# MF_badge_2021_rev_B.net
KiCad netlist of a schematic drawn in EAGLE
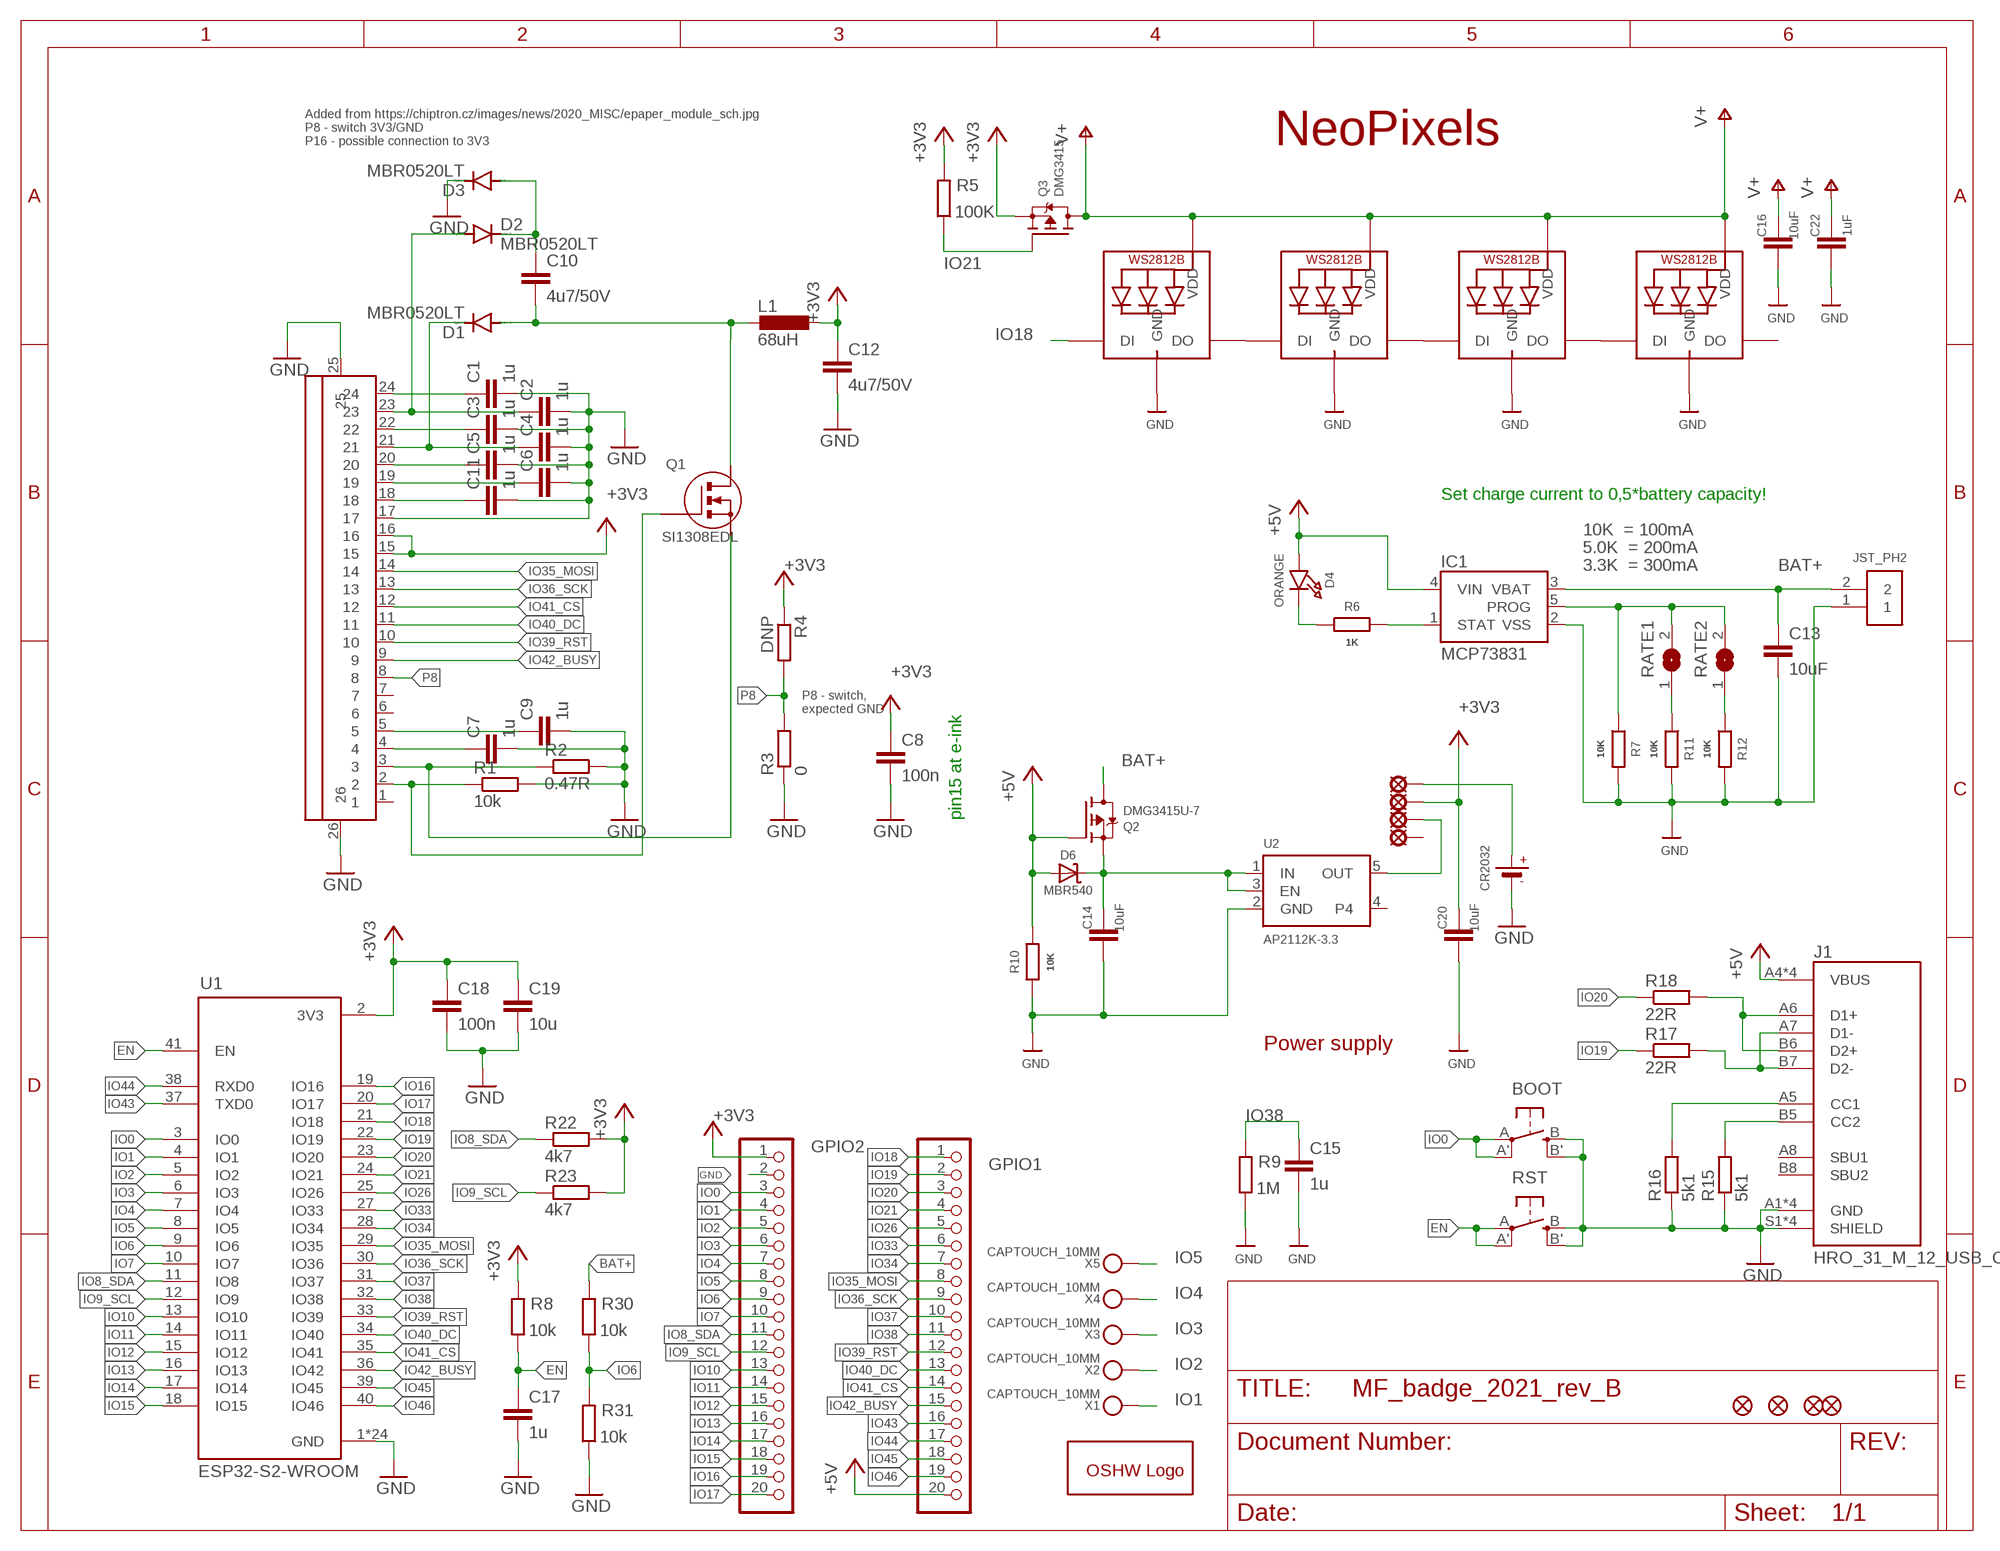
[diagram p0: schematic, sheet 1]

(export (version "E")
  (design (tool "Eeschema 10.0.6"))
  (components
    (comp (ref "BOOT")
      (value "BUTTON_KMR2_4.6X2.8")
      (footprint "eagle-import:BUTTON_KMR2_4.6X2.8")
      (libsource (lib "eagle-import") (part "BUTTON_KMR2_4.6X2.8"))
    )
    (comp (ref "C1")
      (value "1u")
      (footprint "eagle-import:C0805")
      (libsource (lib "eagle-import") (part "C-EUC0805"))
    )
    (comp (ref "C2")
      (value "1u")
      (footprint "eagle-import:C0805")
      (libsource (lib "eagle-import") (part "C-EUC0805"))
    )
    (comp (ref "C3")
      (value "1u")
      (footprint "eagle-import:C0805")
      (libsource (lib "eagle-import") (part "C-EUC0805"))
    )
    (comp (ref "C4")
      (value "1u")
      (footprint "eagle-import:C0805")
      (libsource (lib "eagle-import") (part "C-EUC0805"))
    )
    (comp (ref "C5")
      (value "1u")
      (footprint "eagle-import:C0805")
      (libsource (lib "eagle-import") (part "C-EUC0805"))
    )
    (comp (ref "C6")
      (value "1u")
      (footprint "eagle-import:C0805")
      (libsource (lib "eagle-import") (part "C-EUC0805"))
    )
    (comp (ref "C7")
      (value "1u")
      (footprint "eagle-import:C0805")
      (libsource (lib "eagle-import") (part "C-EUC0805"))
    )
    (comp (ref "C8")
      (value "100n")
      (footprint "eagle-import:C0805")
      (libsource (lib "eagle-import") (part "C-EUC0805"))
    )
    (comp (ref "C9")
      (value "1u")
      (footprint "eagle-import:C0805")
      (libsource (lib "eagle-import") (part "C-EUC0805"))
    )
    (comp (ref "C10")
      (value "4u7/50V")
      (footprint "eagle-import:C0805")
      (libsource (lib "eagle-import") (part "C-EUC0805"))
    )
    (comp (ref "C11")
      (value "1u")
      (footprint "eagle-import:C0805")
      (libsource (lib "eagle-import") (part "C-EUC0805"))
    )
    (comp (ref "C12")
      (value "4u7/50V")
      (footprint "eagle-import:C0805")
      (libsource (lib "eagle-import") (part "C-EUC0805"))
    )
    (comp (ref "C13")
      (value "10uF")
      (footprint "eagle-import:C0805")
      (libsource (lib "eagle-import") (part "C-EUC0805"))
    )
    (comp (ref "C14")
      (value "10uF")
      (footprint "eagle-import:C0805")
      (libsource (lib "eagle-import") (part "C-EUC0805"))
    )
    (comp (ref "C15")
      (value "1u")
      (footprint "eagle-import:C0805")
      (libsource (lib "eagle-import") (part "C-EUC0805"))
    )
    (comp (ref "C16")
      (value "10uF")
      (footprint "eagle-import:C0805")
      (libsource (lib "eagle-import") (part "C-EUC0805"))
    )
    (comp (ref "C17")
      (value "1u")
      (footprint "eagle-import:C0805")
      (libsource (lib "eagle-import") (part "C-EUC0805"))
    )
    (comp (ref "C18")
      (value "100n")
      (footprint "eagle-import:C0805")
      (libsource (lib "eagle-import") (part "C-EUC0805"))
    )
    (comp (ref "C19")
      (value "10u")
      (footprint "eagle-import:C1206")
      (libsource (lib "eagle-import") (part "C-EUC1206"))
    )
    (comp (ref "C20")
      (value "10uF")
      (footprint "eagle-import:C0805")
      (libsource (lib "eagle-import") (part "C-EUC0805"))
    )
    (comp (ref "C22")
      (value "1uF")
      (footprint "eagle-import:C0805")
      (libsource (lib "eagle-import") (part "C-EUC0805"))
    )
    (comp (ref "CR2032")
      (value "BATTERYCR2032_BAT-HLD-001")
      (footprint "eagle-import:CR2032_SMT_BAT-HLD-001")
      (libsource (lib "eagle-import") (part "BATTERYCR2032_BAT-HLD-001"))
    )
    (comp (ref "D1")
      (value "MBR0520LT")
      (footprint "eagle-import:SOD123")
      (libsource (lib "eagle-import") (part "MBR0520LT"))
    )
    (comp (ref "D2")
      (value "MBR0520LT")
      (footprint "eagle-import:SOD123")
      (libsource (lib "eagle-import") (part "MBR0520LT"))
    )
    (comp (ref "D3")
      (value "MBR0520LT")
      (footprint "eagle-import:SOD123")
      (libsource (lib "eagle-import") (part "MBR0520LT"))
    )
    (comp (ref "D4")
      (value "ORANGE")
      (footprint "eagle-import:CHIPLED_0805_NOOUTLINE")
      (libsource (lib "eagle-import") (part "LED0805_NOOUTLINE"))
    )
    (comp (ref "D6")
      (value "MBR540")
      (footprint "eagle-import:SOD-123")
      (libsource (lib "eagle-import") (part "DIODE-SCHOTTKYSOD-123"))
    )
    (comp (ref "FID1")
      (value "FIDUCIAL_1MM")
      (footprint "eagle-import:FIDUCIAL_1MM")
      (libsource (lib "eagle-import") (part "FIDUCIAL_1MM"))
    )
    (comp (ref "FID2")
      (value "FIDUCIAL_1MM")
      (footprint "eagle-import:FIDUCIAL_1MM")
      (libsource (lib "eagle-import") (part "FIDUCIAL_1MM"))
    )
    (comp (ref "FID3")
      (value "FIDUCIAL_1MM")
      (footprint "eagle-import:FIDUCIAL_1MM")
      (libsource (lib "eagle-import") (part "FIDUCIAL_1MM"))
    )
    (comp (ref "FID4")
      (value "FIDUCIAL_1MM")
      (footprint "eagle-import:FIDUCIAL_1MM")
      (libsource (lib "eagle-import") (part "FIDUCIAL_1MM"))
    )
    (comp (ref "GOLD_ORB_SM1")
      (value "OSHWLOGO_")
      (footprint "eagle-import:OSHW_5MM_LOGO")
      (libsource (lib "eagle-import") (part "OSHWLOGO_"))
    )
    (comp (ref "GPIO1")
      (value "PINHD-1X20")
      (footprint "eagle-import:1X20")
      (libsource (lib "eagle-import") (part "PINHD-1X20"))
    )
    (comp (ref "GPIO2")
      (value "PINHD-1X20")
      (footprint "eagle-import:1X20")
      (libsource (lib "eagle-import") (part "PINHD-1X20"))
    )
    (comp (ref "IC1")
      (value "MCP73831")
      (footprint "eagle-import:SOT95P290X120-5")
      (libsource (lib "eagle-import") (part "MCP73831"))
    )
    (comp (ref "J1")
      (value "HRO_31_M_12_USB_C")
      (footprint "eagle-import:HRO_31_M_12_USB_C")
      (libsource (lib "eagle-import") (part "HRO_31_M_12_USB_C"))
    )
    (comp (ref "L1")
      (value "68uH")
      (footprint "eagle-import:L4532P")
      (libsource (lib "eagle-import") (part "L-EUL4532P"))
    )
    (comp (ref "LED2")
      (value "WS2812B5050")
      (footprint "eagle-import:WS2812B")
      (libsource (lib "eagle-import") (part "WS2812B5050"))
    )
    (comp (ref "LED3")
      (value "WS2812B5050")
      (footprint "eagle-import:WS2812B")
      (libsource (lib "eagle-import") (part "WS2812B5050"))
    )
    (comp (ref "LED4")
      (value "WS2812B5050")
      (footprint "eagle-import:WS2812B")
      (libsource (lib "eagle-import") (part "WS2812B5050"))
    )
    (comp (ref "LED5")
      (value "WS2812B5050")
      (footprint "eagle-import:WS2812B")
      (libsource (lib "eagle-import") (part "WS2812B5050"))
    )
    (comp (ref "LSP1")
      (value "MCS10B")
      (footprint "eagle-import:MCS10B")
      (libsource (lib "eagle-import") (part "MCS10B"))
    )
    (comp (ref "LSP2")
      (value "MCS10B")
      (footprint "eagle-import:MCS10B")
      (libsource (lib "eagle-import") (part "MCS10B"))
    )
    (comp (ref "LSP3")
      (value "MCS10B")
      (footprint "eagle-import:MCS10B")
      (libsource (lib "eagle-import") (part "MCS10B"))
    )
    (comp (ref "LSP4")
      (value "MCS10B")
      (footprint "eagle-import:MCS10B")
      (libsource (lib "eagle-import") (part "MCS10B"))
    )
    (comp (ref "Q1")
      (value "SI1308EDL")
      (footprint "eagle-import:SC-70")
      (libsource (lib "eagle-import") (part "SI1308EDL"))
    )
    (comp (ref "Q2")
      (value "DMG3415U-7")
      (footprint "eagle-import:SOT23-R")
      (libsource (lib "eagle-import") (part "MOSFET-P"))
    )
    (comp (ref "Q3")
      (value "DMG3415")
      (footprint "eagle-import:SOT23-R")
      (libsource (lib "eagle-import") (part "MOSFET-P"))
    )
    (comp (ref "R1")
      (value "10k")
      (footprint "eagle-import:R0805")
      (libsource (lib "eagle-import") (part "R-EU_R0805"))
    )
    (comp (ref "R2")
      (value "0.47R")
      (footprint "eagle-import:R0805")
      (libsource (lib "eagle-import") (part "R-EU_R0805"))
    )
    (comp (ref "R3")
      (value "0")
      (footprint "eagle-import:R0805")
      (libsource (lib "eagle-import") (part "R-EU_R0805"))
    )
    (comp (ref "R4")
      (value "DNP")
      (footprint "eagle-import:R0805")
      (libsource (lib "eagle-import") (part "R-EU_R0805"))
    )
    (comp (ref "R5")
      (value "100K")
      (footprint "eagle-import:R0805")
      (libsource (lib "eagle-import") (part "R-EU_R0805"))
    )
    (comp (ref "R6")
      (value "1K")
      (footprint "eagle-import:R0805")
      (libsource (lib "eagle-import") (part "R-EU_R0805"))
    )
    (comp (ref "R7")
      (value "10K")
      (footprint "eagle-import:R0805")
      (libsource (lib "eagle-import") (part "R-EU_R0805"))
    )
    (comp (ref "R8")
      (value "10k")
      (footprint "eagle-import:R0805")
      (libsource (lib "eagle-import") (part "R-EU_R0805"))
    )
    (comp (ref "R9")
      (value "1M")
      (footprint "eagle-import:R0805")
      (libsource (lib "eagle-import") (part "R-EU_R0805"))
    )
    (comp (ref "R10")
      (value "10K")
      (footprint "eagle-import:R0805")
      (libsource (lib "eagle-import") (part "R-EU_R0805"))
    )
    (comp (ref "R11")
      (value "10K")
      (footprint "eagle-import:R0805")
      (libsource (lib "eagle-import") (part "R-EU_R0805"))
    )
    (comp (ref "R12")
      (value "10K")
      (footprint "eagle-import:R0805")
      (libsource (lib "eagle-import") (part "R-EU_R0805"))
    )
    (comp (ref "R15")
      (value "5k1")
      (footprint "eagle-import:R0805")
      (libsource (lib "eagle-import") (part "R-EU_R0805"))
    )
    (comp (ref "R16")
      (value "5k1")
      (footprint "eagle-import:R0805")
      (libsource (lib "eagle-import") (part "R-EU_R0805"))
    )
    (comp (ref "R17")
      (value "22R")
      (footprint "eagle-import:R0805")
      (libsource (lib "eagle-import") (part "R-EU_R0805"))
    )
    (comp (ref "R18")
      (value "22R")
      (footprint "eagle-import:R0805")
      (libsource (lib "eagle-import") (part "R-EU_R0805"))
    )
    (comp (ref "R22")
      (value "4k7")
      (footprint "eagle-import:R0805")
      (libsource (lib "eagle-import") (part "R-EU_R0805"))
    )
    (comp (ref "R23")
      (value "4k7")
      (footprint "eagle-import:R0805")
      (libsource (lib "eagle-import") (part "R-EU_R0805"))
    )
    (comp (ref "R30")
      (value "10k")
      (footprint "eagle-import:R0805")
      (libsource (lib "eagle-import") (part "R-EU_R0805"))
    )
    (comp (ref "R31")
      (value "10k")
      (footprint "eagle-import:R0805")
      (libsource (lib "eagle-import") (part "R-EU_R0805"))
    )
    (comp (ref "RATE1")
      (value "SOLDERJUMPER")
      (footprint "eagle-import:SOLDERJUMPER_ARROW_NOPASTE")
      (libsource (lib "eagle-import") (part "SOLDERJUMPER"))
    )
    (comp (ref "RATE2")
      (value "SOLDERJUMPER")
      (footprint "eagle-import:SOLDERJUMPER_ARROW_NOPASTE")
      (libsource (lib "eagle-import") (part "SOLDERJUMPER"))
    )
    (comp (ref "RST")
      (value "BUTTON_KMR2_4.6X2.8")
      (footprint "eagle-import:BUTTON_KMR2_4.6X2.8")
      (libsource (lib "eagle-import") (part "BUTTON_KMR2_4.6X2.8"))
    )
    (comp (ref "U$1")
      (value "2.13_EINK")
      (footprint "eagle-import:2.13_EINK")
      (libsource (lib "eagle-import") (part "2.13_EINK"))
    )
    (comp (ref "U$8")
      (value "JST_PH2")
      (footprint "eagle-import:JSTPH2")
      (libsource (lib "eagle-import") (part "JST_PH2"))
    )
    (comp (ref "U1")
      (value "ESP32-S2-WROOM")
      (footprint "eagle-import:XCVR_ESP32-S2-WROOM")
      (fields (field (name "MF") "Espressif Systems"))
      (libsource (lib "eagle-import") (part "ESP32-S2-WROOM"))
    )
    (comp (ref "U2")
      (value "AP2112K-3.3")
      (footprint "eagle-import:SOT23-5")
      (libsource (lib "eagle-import") (part "VREG_SOT23-5"))
    )
    (comp (ref "X1")
      (value "CAPTOUCH_10MM")
      (footprint "eagle-import:CAPTOUCH_6X9MM")
      (libsource (lib "eagle-import") (part "CAPTOUCH_MONOPAD_6X9"))
    )
    (comp (ref "X2")
      (value "CAPTOUCH_10MM")
      (footprint "eagle-import:CAPTOUCH_6X9MM")
      (libsource (lib "eagle-import") (part "CAPTOUCH_MONOPAD_6X9"))
    )
    (comp (ref "X3")
      (value "CAPTOUCH_10MM")
      (footprint "eagle-import:CAPTOUCH_6X9MM")
      (libsource (lib "eagle-import") (part "CAPTOUCH_MONOPAD_6X9"))
    )
    (comp (ref "X4")
      (value "CAPTOUCH_10MM")
      (footprint "eagle-import:CAPTOUCH_6X9MM")
      (libsource (lib "eagle-import") (part "CAPTOUCH_MONOPAD_6X9"))
    )
    (comp (ref "X5")
      (value "CAPTOUCH_10MM")
      (footprint "eagle-import:CAPTOUCH_6X9MM")
      (libsource (lib "eagle-import") (part "CAPTOUCH_MONOPAD_6X9"))
    )
  )
  (nets
    (net (code "1") (name "+3V3") (class "Default")
      (node (ref "C12") (pin "1") (pinfunction "1_1") (pintype "passive"))
      (node (ref "C18") (pin "1") (pinfunction "1_1") (pintype "passive"))
      (node (ref "C19") (pin "1") (pinfunction "1_1") (pintype "passive"))
      (node (ref "C20") (pin "1") (pinfunction "1_1") (pintype "passive"))
      (node (ref "C8") (pin "1") (pinfunction "1_1") (pintype "passive"))
      (node (ref "GPIO2") (pin "1") (pinfunction "1_1") (pintype "passive"))
      (node (ref "L1") (pin "1") (pinfunction "1_1") (pintype "passive"))
      (node (ref "LSP2") (pin "MP") (pinfunction "MP_MP") (pintype "passive"))
      (node (ref "Q3") (pin "2") (pinfunction "S_2") (pintype "passive"))
      (node (ref "R22") (pin "2") (pinfunction "2_2") (pintype "passive"))
      (node (ref "R23") (pin "2") (pinfunction "2_2") (pintype "passive"))
      (node (ref "R4") (pin "1") (pinfunction "1_1") (pintype "passive"))
      (node (ref "R5") (pin "2") (pinfunction "2_2") (pintype "passive"))
      (node (ref "R8") (pin "2") (pinfunction "2_2") (pintype "passive"))
      (node (ref "U$1") (pin "15") (pinfunction "15_15") (pintype "bidirectional"))
      (node (ref "U$1") (pin "16") (pinfunction "16_16") (pintype "bidirectional"))
      (node (ref "U1") (pin "2") (pinfunction "3V3_2") (pintype "power_in"))
    )
    (net (code "2") (name "+5V") (class "Default")
      (node (ref "D4") (pin "A") (pinfunction "A_A") (pintype "passive"))
      (node (ref "D6") (pin "A") (pinfunction "A_A") (pintype "passive"))
      (node (ref "GPIO1") (pin "20") (pinfunction "20_20") (pintype "passive"))
      (node (ref "IC1") (pin "4") (pinfunction "VIN_4") (pintype "power_in"))
      (node (ref "J1") (pin "A4") (pinfunction "VBUS_A4") (pintype "passive"))
      (node (ref "J1") (pin "A9") (pinfunction "VBUS_A9") (pintype "passive"))
      (node (ref "J1") (pin "B4") (pinfunction "VBUS_B4") (pintype "passive"))
      (node (ref "J1") (pin "B9") (pinfunction "VBUS_B9") (pintype "passive"))
      (node (ref "Q2") (pin "1") (pinfunction "G_1") (pintype "passive"))
      (node (ref "R10") (pin "2") (pinfunction "2_2") (pintype "passive"))
    )
    (net (code "3") (name "BAT+") (class "Default")
      (node (ref "C13") (pin "1") (pinfunction "1_1") (pintype "passive"))
      (node (ref "IC1") (pin "3") (pinfunction "VBAT_3") (pintype "power_in"))
      (node (ref "Q2") (pin "3") (pinfunction "D_3") (pintype "passive"))
      (node (ref "R30") (pin "2") (pinfunction "2_2") (pintype "passive"))
      (node (ref "U$8") (pin "2") (pinfunction "2_2") (pintype "bidirectional"))
    )
    (net (code "4") (name "EN") (class "Default")
      (node (ref "C17") (pin "1") (pinfunction "1_1") (pintype "passive"))
      (node (ref "R8") (pin "1") (pinfunction "1_1") (pintype "passive"))
      (node (ref "RST") (pin "A") (pinfunction "P_A") (pintype "passive"))
      (node (ref "RST") (pin "A'") (pinfunction "P1_A'") (pintype "passive"))
      (node (ref "U1") (pin "41") (pinfunction "EN_41") (pintype "input"))
    )
    (net (code "5") (name "GND") (class "Default")
      (node (ref "BOOT") (pin "B") (pinfunction "S_B") (pintype "passive"))
      (node (ref "BOOT") (pin "B'") (pinfunction "S1_B'") (pintype "passive"))
      (node (ref "C1") (pin "2") (pinfunction "2_2") (pintype "passive"))
      (node (ref "C11") (pin "2") (pinfunction "2_2") (pintype "passive"))
      (node (ref "C12") (pin "2") (pinfunction "2_2") (pintype "passive"))
      (node (ref "C13") (pin "2") (pinfunction "2_2") (pintype "passive"))
      (node (ref "C14") (pin "2") (pinfunction "2_2") (pintype "passive"))
      (node (ref "C15") (pin "2") (pinfunction "2_2") (pintype "passive"))
      (node (ref "C16") (pin "2") (pinfunction "2_2") (pintype "passive"))
      (node (ref "C17") (pin "2") (pinfunction "2_2") (pintype "passive"))
      (node (ref "C18") (pin "2") (pinfunction "2_2") (pintype "passive"))
      (node (ref "C19") (pin "2") (pinfunction "2_2") (pintype "passive"))
      (node (ref "C2") (pin "2") (pinfunction "2_2") (pintype "passive"))
      (node (ref "C20") (pin "2") (pinfunction "2_2") (pintype "passive"))
      (node (ref "C22") (pin "2") (pinfunction "2_2") (pintype "passive"))
      (node (ref "C3") (pin "2") (pinfunction "2_2") (pintype "passive"))
      (node (ref "C4") (pin "2") (pinfunction "2_2") (pintype "passive"))
      (node (ref "C5") (pin "2") (pinfunction "2_2") (pintype "passive"))
      (node (ref "C6") (pin "2") (pinfunction "2_2") (pintype "passive"))
      (node (ref "C7") (pin "2") (pinfunction "2_2") (pintype "passive"))
      (node (ref "C8") (pin "2") (pinfunction "2_2") (pintype "passive"))
      (node (ref "C9") (pin "2") (pinfunction "2_2") (pintype "passive"))
      (node (ref "CR2032") (pin "-") (pinfunction "-_-") (pintype "passive"))
      (node (ref "D3") (pin "C") (pinfunction "C_C") (pintype "passive"))
      (node (ref "GPIO2") (pin "2") (pinfunction "2_2") (pintype "passive"))
      (node (ref "IC1") (pin "2") (pinfunction "VSS_2") (pintype "power_in"))
      (node (ref "J1") (pin "A1") (pinfunction "GND_A1") (pintype "passive"))
      (node (ref "J1") (pin "A12") (pinfunction "GND_A12") (pintype "passive"))
      (node (ref "J1") (pin "B1") (pinfunction "GND_B1") (pintype "passive"))
      (node (ref "J1") (pin "B12") (pinfunction "GND_B12") (pintype "passive"))
      (node (ref "J1") (pin "S1") (pinfunction "SHIELD_S1") (pintype "passive"))
      (node (ref "J1") (pin "S2") (pinfunction "SHIELD_S2") (pintype "passive"))
      (node (ref "J1") (pin "S3") (pinfunction "SHIELD_S3") (pintype "passive"))
      (node (ref "J1") (pin "S4") (pinfunction "SHIELD_S4") (pintype "passive"))
      (node (ref "LED2") (pin "3-GND") (pinfunction "GND_3-GND") (pintype "power_in"))
      (node (ref "LED3") (pin "3-GND") (pinfunction "GND_3-GND") (pintype "power_in"))
      (node (ref "LED4") (pin "3-GND") (pinfunction "GND_3-GND") (pintype "power_in"))
      (node (ref "LED5") (pin "3-GND") (pinfunction "GND_3-GND") (pintype "power_in"))
      (node (ref "R1") (pin "2") (pinfunction "2_2") (pintype "passive"))
      (node (ref "R10") (pin "1") (pinfunction "1_1") (pintype "passive"))
      (node (ref "R11") (pin "2") (pinfunction "2_2") (pintype "passive"))
      (node (ref "R12") (pin "2") (pinfunction "2_2") (pintype "passive"))
      (node (ref "R15") (pin "1") (pinfunction "1_1") (pintype "passive"))
      (node (ref "R16") (pin "1") (pinfunction "1_1") (pintype "passive"))
      (node (ref "R2") (pin "2") (pinfunction "2_2") (pintype "passive"))
      (node (ref "R3") (pin "1") (pinfunction "1_1") (pintype "passive"))
      (node (ref "R31") (pin "1") (pinfunction "1_1") (pintype "passive"))
      (node (ref "R7") (pin "2") (pinfunction "2_2") (pintype "passive"))
      (node (ref "R9") (pin "1") (pinfunction "1_1") (pintype "passive"))
      (node (ref "RST") (pin "B") (pinfunction "S_B") (pintype "passive"))
      (node (ref "RST") (pin "B'") (pinfunction "S1_B'") (pintype "passive"))
      (node (ref "U$1") (pin "17") (pinfunction "17_17") (pintype "bidirectional"))
      (node (ref "U$1") (pin "25") (pinfunction "25_25") (pintype "power_in"))
      (node (ref "U$1") (pin "26") (pinfunction "26_26") (pintype "power_in"))
      (node (ref "U$8") (pin "1") (pinfunction "1_1") (pintype "bidirectional"))
      (node (ref "U1") (pin "1") (pinfunction "GND_1") (pintype "power_in"))
      (node (ref "U1") (pin "26") (pinfunction "GND_26") (pintype "power_in"))
      (node (ref "U1") (pin "42") (pinfunction "GND_42") (pintype "power_in"))
      (node (ref "U1") (pin "43.1") (pinfunction "GND_43.1") (pintype "power_in"))
      (node (ref "U1") (pin "43.10") (pinfunction "GND_43.10") (pintype "power_in"))
      (node (ref "U1") (pin "43.11") (pinfunction "GND_43.11") (pintype "power_in"))
      (node (ref "U1") (pin "43.12") (pinfunction "GND_43.12") (pintype "power_in"))
      (node (ref "U1") (pin "43.13") (pinfunction "GND_43.13") (pintype "power_in"))
      (node (ref "U1") (pin "43.14") (pinfunction "GND_43.14") (pintype "power_in"))
      (node (ref "U1") (pin "43.15") (pinfunction "GND_43.15") (pintype "power_in"))
      (node (ref "U1") (pin "43.16") (pinfunction "GND_43.16") (pintype "power_in"))
      (node (ref "U1") (pin "43.17") (pinfunction "GND_43.17") (pintype "power_in"))
      (node (ref "U1") (pin "43.18") (pinfunction "GND_43.18") (pintype "power_in"))
      (node (ref "U1") (pin "43.19") (pinfunction "GND_43.19") (pintype "power_in"))
      (node (ref "U1") (pin "43.2") (pinfunction "GND_43.2") (pintype "power_in"))
      (node (ref "U1") (pin "43.20") (pinfunction "GND_43.20") (pintype "power_in"))
      (node (ref "U1") (pin "43.21") (pinfunction "GND_43.21") (pintype "power_in"))
      (node (ref "U1") (pin "43.3") (pinfunction "GND_43.3") (pintype "power_in"))
      (node (ref "U1") (pin "43.4") (pinfunction "GND_43.4") (pintype "power_in"))
      (node (ref "U1") (pin "43.5") (pinfunction "GND_43.5") (pintype "power_in"))
      (node (ref "U1") (pin "43.6") (pinfunction "GND_43.6") (pintype "power_in"))
      (node (ref "U1") (pin "43.7") (pinfunction "GND_43.7") (pintype "power_in"))
      (node (ref "U1") (pin "43.8") (pinfunction "GND_43.8") (pintype "power_in"))
      (node (ref "U1") (pin "43.9") (pinfunction "GND_43.9") (pintype "power_in"))
      (node (ref "U2") (pin "2") (pinfunction "GND_2") (pintype "power_in"))
    )
    (net (code "6") (name "IO0") (class "Default")
      (node (ref "BOOT") (pin "A") (pinfunction "P_A") (pintype "passive"))
      (node (ref "BOOT") (pin "A'") (pinfunction "P1_A'") (pintype "passive"))
      (node (ref "GPIO2") (pin "3") (pinfunction "3_3") (pintype "passive"))
      (node (ref "U1") (pin "3") (pinfunction "IO0_3") (pintype "bidirectional"))
    )
    (net (code "7") (name "IO1") (class "Default")
      (node (ref "GPIO2") (pin "4") (pinfunction "4_4") (pintype "passive"))
      (node (ref "U1") (pin "4") (pinfunction "IO1_4") (pintype "bidirectional"))
      (node (ref "X1") (pin "P$1") (pinfunction "P$1_P$1") (pintype "bidirectional"))
    )
    (net (code "8") (name "IO2") (class "Default")
      (node (ref "GPIO2") (pin "5") (pinfunction "5_5") (pintype "passive"))
      (node (ref "U1") (pin "5") (pinfunction "IO2_5") (pintype "bidirectional"))
      (node (ref "X2") (pin "P$1") (pinfunction "P$1_P$1") (pintype "bidirectional"))
    )
    (net (code "9") (name "IO3") (class "Default")
      (node (ref "GPIO2") (pin "6") (pinfunction "6_6") (pintype "passive"))
      (node (ref "U1") (pin "6") (pinfunction "IO3_6") (pintype "bidirectional"))
      (node (ref "X3") (pin "P$1") (pinfunction "P$1_P$1") (pintype "bidirectional"))
    )
    (net (code "10") (name "IO4") (class "Default")
      (node (ref "GPIO2") (pin "7") (pinfunction "7_7") (pintype "passive"))
      (node (ref "U1") (pin "7") (pinfunction "IO4_7") (pintype "bidirectional"))
      (node (ref "X4") (pin "P$1") (pinfunction "P$1_P$1") (pintype "bidirectional"))
    )
    (net (code "11") (name "IO5") (class "Default")
      (node (ref "GPIO2") (pin "8") (pinfunction "8_8") (pintype "passive"))
      (node (ref "U1") (pin "8") (pinfunction "IO5_8") (pintype "bidirectional"))
      (node (ref "X5") (pin "P$1") (pinfunction "P$1_P$1") (pintype "bidirectional"))
    )
    (net (code "12") (name "IO6") (class "Default")
      (node (ref "GPIO2") (pin "9") (pinfunction "9_9") (pintype "passive"))
      (node (ref "R30") (pin "1") (pinfunction "1_1") (pintype "passive"))
      (node (ref "R31") (pin "2") (pinfunction "2_2") (pintype "passive"))
      (node (ref "U1") (pin "9") (pinfunction "IO6_9") (pintype "bidirectional"))
    )
    (net (code "13") (name "IO7") (class "Default")
      (node (ref "GPIO2") (pin "10") (pinfunction "10_10") (pintype "passive"))
      (node (ref "U1") (pin "10") (pinfunction "IO7_10") (pintype "bidirectional"))
    )
    (net (code "14") (name "IO8_SDA") (class "Default")
      (node (ref "GPIO2") (pin "11") (pinfunction "11_11") (pintype "passive"))
      (node (ref "R22") (pin "1") (pinfunction "1_1") (pintype "passive"))
      (node (ref "U1") (pin "11") (pinfunction "IO8_11") (pintype "bidirectional"))
    )
    (net (code "15") (name "IO9_SCL") (class "Default")
      (node (ref "GPIO2") (pin "12") (pinfunction "12_12") (pintype "passive"))
      (node (ref "R23") (pin "1") (pinfunction "1_1") (pintype "passive"))
      (node (ref "U1") (pin "12") (pinfunction "IO9_12") (pintype "bidirectional"))
    )
    (net (code "16") (name "IO10") (class "Default")
      (node (ref "GPIO2") (pin "13") (pinfunction "13_13") (pintype "passive"))
      (node (ref "U1") (pin "13") (pinfunction "IO10_13") (pintype "bidirectional"))
    )
    (net (code "17") (name "IO11") (class "Default")
      (node (ref "GPIO2") (pin "14") (pinfunction "14_14") (pintype "passive"))
      (node (ref "U1") (pin "14") (pinfunction "IO11_14") (pintype "bidirectional"))
    )
    (net (code "18") (name "IO12") (class "Default")
      (node (ref "GPIO2") (pin "15") (pinfunction "15_15") (pintype "passive"))
      (node (ref "U1") (pin "15") (pinfunction "IO12_15") (pintype "bidirectional"))
    )
    (net (code "19") (name "IO13") (class "Default")
      (node (ref "GPIO2") (pin "16") (pinfunction "16_16") (pintype "passive"))
      (node (ref "U1") (pin "16") (pinfunction "IO13_16") (pintype "bidirectional"))
    )
    (net (code "20") (name "IO14") (class "Default")
      (node (ref "GPIO2") (pin "17") (pinfunction "17_17") (pintype "passive"))
      (node (ref "U1") (pin "17") (pinfunction "IO14_17") (pintype "bidirectional"))
    )
    (net (code "21") (name "IO15") (class "Default")
      (node (ref "GPIO2") (pin "18") (pinfunction "18_18") (pintype "passive"))
      (node (ref "U1") (pin "18") (pinfunction "IO15_18") (pintype "bidirectional"))
    )
    (net (code "22") (name "IO16") (class "Default")
      (node (ref "GPIO2") (pin "19") (pinfunction "19_19") (pintype "passive"))
      (node (ref "U1") (pin "19") (pinfunction "IO16_19") (pintype "bidirectional"))
    )
    (net (code "23") (name "IO17") (class "Default")
      (node (ref "GPIO2") (pin "20") (pinfunction "20_20") (pintype "passive"))
      (node (ref "U1") (pin "20") (pinfunction "IO17_20") (pintype "bidirectional"))
    )
    (net (code "24") (name "IO18") (class "Default")
      (node (ref "GPIO1") (pin "1") (pinfunction "1_1") (pintype "passive"))
      (node (ref "LED2") (pin "4-DIN") (pinfunction "DI_4-DIN") (pintype "input"))
      (node (ref "U1") (pin "21") (pinfunction "IO18_21") (pintype "bidirectional"))
    )
    (net (code "25") (name "IO19") (class "Default")
      (node (ref "GPIO1") (pin "2") (pinfunction "2_2") (pintype "passive"))
      (node (ref "R17") (pin "1") (pinfunction "1_1") (pintype "passive"))
      (node (ref "U1") (pin "22") (pinfunction "IO19_22") (pintype "bidirectional"))
    )
    (net (code "26") (name "IO20") (class "Default")
      (node (ref "GPIO1") (pin "3") (pinfunction "3_3") (pintype "passive"))
      (node (ref "R18") (pin "1") (pinfunction "1_1") (pintype "passive"))
      (node (ref "U1") (pin "23") (pinfunction "IO20_23") (pintype "bidirectional"))
    )
    (net (code "27") (name "IO21") (class "Default")
      (node (ref "GPIO1") (pin "4") (pinfunction "4_4") (pintype "passive"))
      (node (ref "Q3") (pin "1") (pinfunction "G_1") (pintype "passive"))
      (node (ref "R5") (pin "1") (pinfunction "1_1") (pintype "passive"))
      (node (ref "U1") (pin "24") (pinfunction "IO21_24") (pintype "bidirectional"))
    )
    (net (code "28") (name "IO26") (class "Default")
      (node (ref "GPIO1") (pin "5") (pinfunction "5_5") (pintype "passive"))
      (node (ref "U1") (pin "25") (pinfunction "IO26_25") (pintype "bidirectional"))
    )
    (net (code "29") (name "IO33") (class "Default")
      (node (ref "GPIO1") (pin "6") (pinfunction "6_6") (pintype "passive"))
      (node (ref "U1") (pin "27") (pinfunction "IO33_27") (pintype "bidirectional"))
    )
    (net (code "30") (name "IO34") (class "Default")
      (node (ref "GPIO1") (pin "7") (pinfunction "7_7") (pintype "passive"))
      (node (ref "U1") (pin "28") (pinfunction "IO34_28") (pintype "bidirectional"))
    )
    (net (code "31") (name "IO35_MOSI") (class "Default")
      (node (ref "GPIO1") (pin "8") (pinfunction "8_8") (pintype "passive"))
      (node (ref "U$1") (pin "14") (pinfunction "14_14") (pintype "bidirectional"))
      (node (ref "U1") (pin "29") (pinfunction "IO35_29") (pintype "bidirectional"))
    )
    (net (code "32") (name "IO36_SCK") (class "Default")
      (node (ref "GPIO1") (pin "9") (pinfunction "9_9") (pintype "passive"))
      (node (ref "U$1") (pin "13") (pinfunction "13_13") (pintype "bidirectional"))
      (node (ref "U1") (pin "30") (pinfunction "IO36_30") (pintype "bidirectional"))
    )
    (net (code "33") (name "IO37") (class "Default")
      (node (ref "GPIO1") (pin "10") (pinfunction "10_10") (pintype "passive"))
      (node (ref "U1") (pin "31") (pinfunction "IO37_31") (pintype "bidirectional"))
    )
    (net (code "34") (name "IO38") (class "Default")
      (node (ref "C15") (pin "1") (pinfunction "1_1") (pintype "passive"))
      (node (ref "GPIO1") (pin "11") (pinfunction "11_11") (pintype "passive"))
      (node (ref "R9") (pin "2") (pinfunction "2_2") (pintype "passive"))
      (node (ref "U1") (pin "32") (pinfunction "IO38_32") (pintype "bidirectional"))
    )
    (net (code "35") (name "IO39_RST") (class "Default")
      (node (ref "GPIO1") (pin "12") (pinfunction "12_12") (pintype "passive"))
      (node (ref "U$1") (pin "10") (pinfunction "10_10") (pintype "bidirectional"))
      (node (ref "U1") (pin "33") (pinfunction "IO39_33") (pintype "bidirectional"))
    )
    (net (code "36") (name "IO40_DC") (class "Default")
      (node (ref "GPIO1") (pin "13") (pinfunction "13_13") (pintype "passive"))
      (node (ref "U$1") (pin "11") (pinfunction "11_11") (pintype "bidirectional"))
      (node (ref "U1") (pin "34") (pinfunction "IO40_34") (pintype "bidirectional"))
    )
    (net (code "37") (name "IO41_CS") (class "Default")
      (node (ref "GPIO1") (pin "14") (pinfunction "14_14") (pintype "passive"))
      (node (ref "U$1") (pin "12") (pinfunction "12_12") (pintype "bidirectional"))
      (node (ref "U1") (pin "35") (pinfunction "IO41_35") (pintype "bidirectional"))
    )
    (net (code "38") (name "IO42_BUSY") (class "Default")
      (node (ref "GPIO1") (pin "15") (pinfunction "15_15") (pintype "passive"))
      (node (ref "U$1") (pin "9") (pinfunction "9_9") (pintype "bidirectional"))
      (node (ref "U1") (pin "36") (pinfunction "IO42_36") (pintype "bidirectional"))
    )
    (net (code "39") (name "IO43") (class "Default")
      (node (ref "GPIO1") (pin "16") (pinfunction "16_16") (pintype "passive"))
      (node (ref "U1") (pin "37") (pinfunction "TXD0_37") (pintype "bidirectional"))
    )
    (net (code "40") (name "IO44") (class "Default")
      (node (ref "GPIO1") (pin "17") (pinfunction "17_17") (pintype "passive"))
      (node (ref "U1") (pin "38") (pinfunction "RXD0_38") (pintype "bidirectional"))
    )
    (net (code "41") (name "IO45") (class "Default")
      (node (ref "GPIO1") (pin "18") (pinfunction "18_18") (pintype "passive"))
      (node (ref "U1") (pin "39") (pinfunction "IO45_39") (pintype "bidirectional"))
    )
    (net (code "42") (name "IO46") (class "Default")
      (node (ref "GPIO1") (pin "19") (pinfunction "19_19") (pintype "passive"))
      (node (ref "U1") (pin "40") (pinfunction "IO46_40") (pintype "bidirectional"))
    )
    (net (code "43") (name "Net-(C1-Pad1)") (class "Default")
      (node (ref "C1") (pin "1") (pinfunction "1_1") (pintype "passive"))
      (node (ref "U$1") (pin "24") (pinfunction "24_24") (pintype "bidirectional"))
    )
    (net (code "44") (name "Net-(C2-Pad1)") (class "Default")
      (node (ref "C2") (pin "1") (pinfunction "1_1") (pintype "passive"))
      (node (ref "D2") (pin "A") (pinfunction "A_A") (pintype "passive"))
      (node (ref "U$1") (pin "23") (pinfunction "23_23") (pintype "bidirectional"))
    )
    (net (code "45") (name "Net-(C3-Pad1)") (class "Default")
      (node (ref "C3") (pin "1") (pinfunction "1_1") (pintype "passive"))
      (node (ref "U$1") (pin "22") (pinfunction "22_22") (pintype "bidirectional"))
    )
    (net (code "46") (name "Net-(C4-Pad1)") (class "Default")
      (node (ref "C4") (pin "1") (pinfunction "1_1") (pintype "passive"))
      (node (ref "D1") (pin "C") (pinfunction "C_C") (pintype "passive"))
      (node (ref "U$1") (pin "21") (pinfunction "21_21") (pintype "bidirectional"))
    )
    (net (code "47") (name "Net-(C5-Pad1)") (class "Default")
      (node (ref "C5") (pin "1") (pinfunction "1_1") (pintype "passive"))
      (node (ref "U$1") (pin "20") (pinfunction "20_20") (pintype "bidirectional"))
    )
    (net (code "48") (name "Net-(C6-Pad1)") (class "Default")
      (node (ref "C6") (pin "1") (pinfunction "1_1") (pintype "passive"))
      (node (ref "U$1") (pin "19") (pinfunction "19_19") (pintype "bidirectional"))
    )
    (net (code "49") (name "Net-(C7-Pad1)") (class "Default")
      (node (ref "C7") (pin "1") (pinfunction "1_1") (pintype "passive"))
      (node (ref "U$1") (pin "4") (pinfunction "4_4") (pintype "bidirectional"))
    )
    (net (code "50") (name "Net-(C9-Pad1)") (class "Default")
      (node (ref "C9") (pin "1") (pinfunction "1_1") (pintype "passive"))
      (node (ref "U$1") (pin "5") (pinfunction "5_5") (pintype "bidirectional"))
    )
    (net (code "51") (name "Net-(C10-Pad1)") (class "Default")
      (node (ref "C10") (pin "1") (pinfunction "1_1") (pintype "passive"))
      (node (ref "D2") (pin "C") (pinfunction "C_C") (pintype "passive"))
      (node (ref "D3") (pin "A") (pinfunction "A_A") (pintype "passive"))
    )
    (net (code "52") (name "Net-(C11-Pad1)") (class "Default")
      (node (ref "C11") (pin "1") (pinfunction "1_1") (pintype "passive"))
      (node (ref "U$1") (pin "18") (pinfunction "18_18") (pintype "bidirectional"))
    )
    (net (code "53") (name "Net-(CR2032-+-Pad+$1)") (class "Default")
      (node (ref "CR2032") (pin "+$1") (pinfunction "+_+$1") (pintype "passive"))
      (node (ref "CR2032") (pin "+$2") (pinfunction "+_+$2") (pintype "passive"))
      (node (ref "LSP1") (pin "MP") (pinfunction "MP_MP") (pintype "passive"))
    )
    (net (code "54") (name "Net-(D4-PadC)") (class "Default")
      (node (ref "D4") (pin "C") (pinfunction "C_C") (pintype "passive"))
      (node (ref "R6") (pin "1") (pinfunction "1_1") (pintype "passive"))
    )
    (net (code "55") (name "Net-(IC1-PROG)") (class "Default")
      (node (ref "IC1") (pin "5") (pinfunction "PROG_5") (pintype "input"))
      (node (ref "R7") (pin "1") (pinfunction "1_1") (pintype "passive"))
      (node (ref "RATE1") (pin "2") (pinfunction "2_2") (pintype "passive"))
      (node (ref "RATE2") (pin "2") (pinfunction "2_2") (pintype "passive"))
    )
    (net (code "56") (name "Net-(IC1-STAT)") (class "Default")
      (node (ref "IC1") (pin "1") (pinfunction "STAT_1") (pintype "output"))
      (node (ref "R6") (pin "2") (pinfunction "2_2") (pintype "passive"))
    )
    (net (code "57") (name "Net-(J1-CC1)") (class "Default")
      (node (ref "J1") (pin "A5") (pinfunction "CC1_A5") (pintype "passive"))
      (node (ref "R16") (pin "2") (pinfunction "2_2") (pintype "passive"))
    )
    (net (code "58") (name "Net-(J1-CC2)") (class "Default")
      (node (ref "J1") (pin "B5") (pinfunction "CC2_B5") (pintype "passive"))
      (node (ref "R15") (pin "2") (pinfunction "2_2") (pintype "passive"))
    )
    (net (code "59") (name "Net-(J1-D1+)") (class "Default")
      (node (ref "J1") (pin "A6") (pinfunction "D1+_A6") (pintype "passive"))
      (node (ref "J1") (pin "B6") (pinfunction "D2+_B6") (pintype "passive"))
      (node (ref "R18") (pin "2") (pinfunction "2_2") (pintype "passive"))
    )
    (net (code "60") (name "Net-(J1-D1-)") (class "Default")
      (node (ref "J1") (pin "A7") (pinfunction "D1-_A7") (pintype "passive"))
      (node (ref "J1") (pin "B7") (pinfunction "D2-_B7") (pintype "passive"))
      (node (ref "R17") (pin "2") (pinfunction "2_2") (pintype "passive"))
    )
    (net (code "61") (name "Net-(LED2-DO)") (class "Default")
      (node (ref "LED2") (pin "2-DOUT") (pinfunction "DO_2-DOUT") (pintype "output"))
      (node (ref "LED3") (pin "4-DIN") (pinfunction "DI_4-DIN") (pintype "input"))
    )
    (net (code "62") (name "Net-(LED3-DO)") (class "Default")
      (node (ref "LED3") (pin "2-DOUT") (pinfunction "DO_2-DOUT") (pintype "output"))
      (node (ref "LED4") (pin "4-DIN") (pinfunction "DI_4-DIN") (pintype "input"))
    )
    (net (code "63") (name "Net-(LED4-DO)") (class "Default")
      (node (ref "LED4") (pin "2-DOUT") (pinfunction "DO_2-DOUT") (pintype "output"))
      (node (ref "LED5") (pin "4-DIN") (pinfunction "DI_4-DIN") (pintype "input"))
    )
    (net (code "64") (name "Net-(Q1-D)") (class "Default")
      (node (ref "C10") (pin "2") (pinfunction "2_2") (pintype "passive"))
      (node (ref "D1") (pin "A") (pinfunction "A_A") (pintype "passive"))
      (node (ref "L1") (pin "2") (pinfunction "2_2") (pintype "passive"))
      (node (ref "Q1") (pin "3") (pinfunction "D_3") (pintype "passive"))
    )
    (net (code "65") (name "Net-(Q1-G)") (class "Default")
      (node (ref "Q1") (pin "1") (pinfunction "G_1") (pintype "passive"))
      (node (ref "R1") (pin "1") (pinfunction "1_1") (pintype "passive"))
      (node (ref "U$1") (pin "2") (pinfunction "2_2") (pintype "bidirectional"))
    )
    (net (code "66") (name "Net-(Q1-S)") (class "Default")
      (node (ref "Q1") (pin "2") (pinfunction "S_2") (pintype "passive"))
      (node (ref "R2") (pin "1") (pinfunction "1_1") (pintype "passive"))
      (node (ref "U$1") (pin "3") (pinfunction "3_3") (pintype "bidirectional"))
    )
    (net (code "67") (name "Net-(Q2-S)") (class "Default")
      (node (ref "C14") (pin "1") (pinfunction "1_1") (pintype "passive"))
      (node (ref "D6") (pin "C") (pinfunction "C_C") (pintype "passive"))
      (node (ref "Q2") (pin "2") (pinfunction "S_2") (pintype "passive"))
      (node (ref "U2") (pin "1") (pinfunction "IN_1") (pintype "power_in"))
      (node (ref "U2") (pin "3") (pinfunction "EN_3") (pintype "input"))
    )
    (net (code "68") (name "Net-(R11-Pad1)") (class "Default")
      (node (ref "R11") (pin "1") (pinfunction "1_1") (pintype "passive"))
      (node (ref "RATE1") (pin "1") (pinfunction "1_1") (pintype "passive"))
    )
    (net (code "69") (name "Net-(R12-Pad1)") (class "Default")
      (node (ref "R12") (pin "1") (pinfunction "1_1") (pintype "passive"))
      (node (ref "RATE2") (pin "1") (pinfunction "1_1") (pintype "passive"))
    )
    (net (code "70") (name "Net-(U2-OUT)") (class "Default")
      (node (ref "LSP3") (pin "MP") (pinfunction "MP_MP") (pintype "passive"))
      (node (ref "U2") (pin "5") (pinfunction "OUT_5") (pintype "power_in"))
    )
    (net (code "71") (name "P8") (class "Default")
      (node (ref "R3") (pin "2") (pinfunction "2_2") (pintype "passive"))
      (node (ref "R4") (pin "2") (pinfunction "2_2") (pintype "passive"))
      (node (ref "U$1") (pin "8") (pinfunction "8_8") (pintype "bidirectional"))
    )
    (net (code "72") (name "V+") (class "Default")
      (node (ref "C16") (pin "1") (pinfunction "1_1") (pintype "passive"))
      (node (ref "C22") (pin "1") (pinfunction "1_1") (pintype "passive"))
      (node (ref "LED2") (pin "1-VDD") (pinfunction "VDD_1-VDD") (pintype "power_in"))
      (node (ref "LED3") (pin "1-VDD") (pinfunction "VDD_1-VDD") (pintype "power_in"))
      (node (ref "LED4") (pin "1-VDD") (pinfunction "VDD_1-VDD") (pintype "power_in"))
      (node (ref "LED5") (pin "1-VDD") (pinfunction "VDD_1-VDD") (pintype "power_in"))
      (node (ref "Q3") (pin "3") (pinfunction "D_3") (pintype "passive"))
    )
    (net (code "73") (name "unconnected-(J1-SBU1-PadA8)") (class "Default")
      (node (ref "J1") (pin "A8") (pinfunction "SBU1_A8") (pintype "passive"))
    )
    (net (code "74") (name "unconnected-(J1-SBU2-PadB8)") (class "Default")
      (node (ref "J1") (pin "B8") (pinfunction "SBU2_B8") (pintype "passive"))
    )
    (net (code "75") (name "unconnected-(LED5-DO-Pad2-DOUT)") (class "Default")
      (node (ref "LED5") (pin "2-DOUT") (pinfunction "DO_2-DOUT") (pintype "output"))
    )
    (net (code "76") (name "unconnected-(LSP4-PadMP)") (class "Default")
      (node (ref "LSP4") (pin "MP") (pinfunction "MP_MP") (pintype "passive"))
    )
    (net (code "77") (name "unconnected-(U$1-Pad1)") (class "Default")
      (node (ref "U$1") (pin "1") (pinfunction "1_1") (pintype "bidirectional"))
    )
    (net (code "78") (name "unconnected-(U$1-Pad6)") (class "Default")
      (node (ref "U$1") (pin "6") (pinfunction "6_6") (pintype "bidirectional"))
    )
    (net (code "79") (name "unconnected-(U$1-Pad7)") (class "Default")
      (node (ref "U$1") (pin "7") (pinfunction "7_7") (pintype "bidirectional"))
    )
    (net (code "80") (name "unconnected-(U2-P4-Pad4)") (class "Default")
      (node (ref "U2") (pin "4") (pinfunction "P4_4") (pintype "bidirectional"))
    )
  )
)
